# Sch_Dr_General.net
KiCad netlist of a schematic drawn in Altium Designer
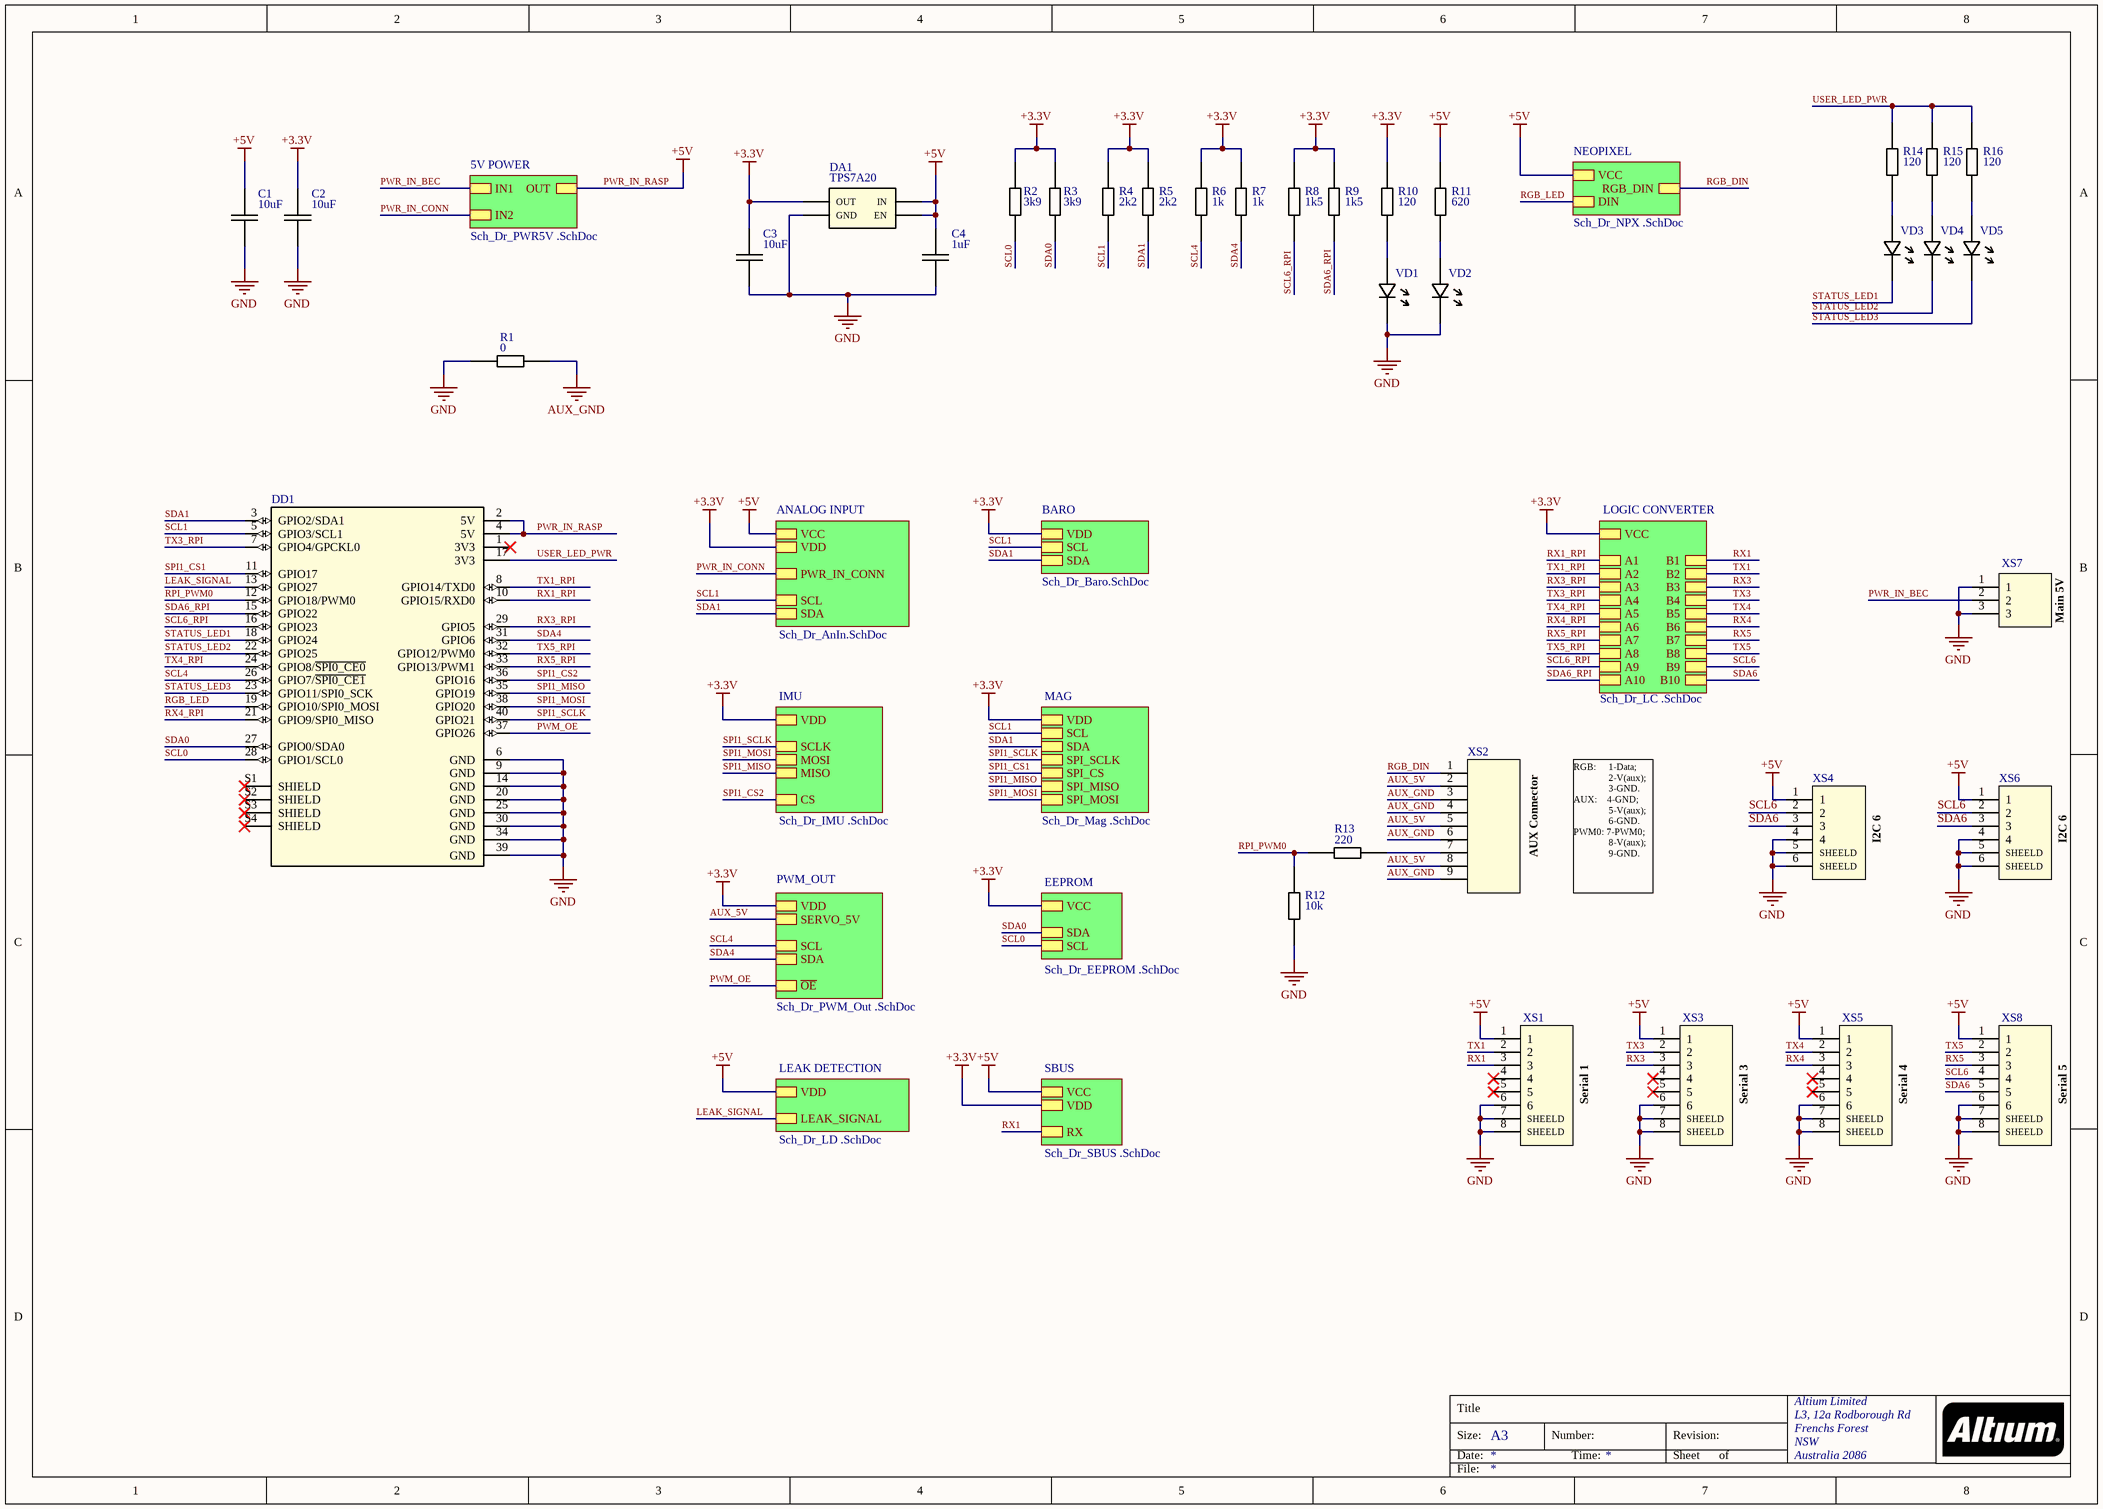
[diagram p0: Sch_Dr_General.SchDoc]

(export (version "E")
  (design (tool "Eeschema 10.0.6"))
  (components
    (comp (ref "C1")
      (value "10uF")
      (footprint "Cap_0603")
      (description "CC0603KRX5R7BB106")
      (libsource (lib "Dr_lib") (part "Cap_"))
    )
    (comp (ref "C2")
      (value "10uF")
      (footprint "Cap_0603")
      (description "CC0603KRX5R7BB106")
      (libsource (lib "Dr_lib") (part "Cap_"))
    )
    (comp (ref "C3")
      (value "10uF")
      (footprint "Cap_0603")
      (description "CC0603KRX5R7BB106")
      (libsource (lib "Dr_lib") (part "Cap_"))
    )
    (comp (ref "C4")
      (value "1uF")
      (footprint "Cap_0603")
      (description "CC0603JRX7R7BB105")
      (libsource (lib "Dr_lib") (part "Cap_"))
    )
    (comp (ref "DA1")
      (value "TPS7A20")
      (footprint "SOT-23-5")
      (description "High PSRR LDO")
      (libsource (lib "Dr_lib") (part "TPS7A20"))
    )
    (comp (ref "DD1")
      (value "RASPBERRY_PI_4")
      (footprint "MOD_RASPBERRY_PI_4B_4GB")
      (description "BCM2711 Raspberry Pi 4 Model B 4GB - ARMÂ® CortexÂ®-A72 MPU Embedded Evaluation Board")
      (fields (field (name "MF") "Raspberry Pi") (field (name "MP") "RASPBERRY PI 4B/4GB"))
      (libsource (lib "Dr_lib") (part "RASPBERRY_PI_4B_4GB"))
    )
    (comp (ref "R1")
      (value "0")
      (footprint "Res_0603")
      (description "CR-03FL7----0R")
      (libsource (lib "") (part "Res__4"))
    )
    (comp (ref "R2")
      (value "3k9")
      (footprint "Res_0603")
      (description "CR-03FL7---3K9")
      (libsource (lib "Dr_lib") (part "Res_"))
    )
    (comp (ref "R3")
      (value "3k9")
      (footprint "Res_0603")
      (description "CR-03FL7---3K9")
      (libsource (lib "Dr_lib") (part "Res_"))
    )
    (comp (ref "R4")
      (value "2k2")
      (footprint "Res_0603")
      (description "CR-03FL7---2K2")
      (libsource (lib "") (part "Res__2"))
    )
    (comp (ref "R5")
      (value "2k2")
      (footprint "Res_0603")
      (description "CR-03FL7---2K2")
      (libsource (lib "") (part "Res__2"))
    )
    (comp (ref "R6")
      (value "1k")
      (footprint "Res_0603")
      (description "CR-03FL7----1K")
      (libsource (lib "") (part "Res__2"))
    )
    (comp (ref "R7")
      (value "1k")
      (footprint "Res_0603")
      (description "CR-03FL7----1K")
      (libsource (lib "") (part "Res__2"))
    )
    (comp (ref "R8")
      (value "1k5")
      (footprint "Res_0603")
      (description "CR-03FL7---1K5")
      (libsource (lib "") (part "Res__2"))
    )
    (comp (ref "R9")
      (value "1k5")
      (footprint "Res_0603")
      (description "CR-03FL7---1K5")
      (libsource (lib "") (part "Res__5"))
    )
    (comp (ref "R10")
      (value "120")
      (footprint "Res_0603")
      (description "CR-03FL7--120R")
      (libsource (lib "") (part "Res__2"))
    )
    (comp (ref "R11")
      (value "620")
      (footprint "Res_0603")
      (description "CR-03FL7--620R")
      (libsource (lib "") (part "Res__2"))
    )
    (comp (ref "R12")
      (value "10k")
      (footprint "Res_0603")
      (description "CR-03FL7---10K")
      (libsource (lib "") (part "Res__3"))
    )
    (comp (ref "R13")
      (value "220")
      (footprint "Res_0603")
      (description "CR-03FL7--220R")
      (libsource (lib "") (part "Res__6"))
    )
    (comp (ref "R14")
      (value "120")
      (footprint "Res_0603")
      (description "CR-03FL7--120R")
      (libsource (lib "") (part "Res__1"))
    )
    (comp (ref "R15")
      (value "120")
      (footprint "Res_0603")
      (description "CR-03FL7---120R")
      (libsource (lib "") (part "Res__1"))
    )
    (comp (ref "R16")
      (value "120")
      (footprint "Res_0603")
      (description "CR-03FL7--120R")
      (libsource (lib "") (part "Res__1"))
    )
    (comp (ref "VD1")
      (value "TO-1608BC-PG")
      (footprint "0603_LED")
      (description "SMD LED Green")
      (libsource (lib "Dr_lib") (part "LED_"))
    )
    (comp (ref "VD2")
      (value "TO-1608BC-PG")
      (footprint "0603_LED")
      (description "SMD LED Green")
      (libsource (lib "Dr_lib") (part "LED_"))
    )
    (comp (ref "VD3")
      (value "TO-1608BC-PG")
      (footprint "0603_LED")
      (description "SMD LED Green")
      (libsource (lib "Dr_lib") (part "LED_"))
    )
    (comp (ref "VD4")
      (value "TO-1608BC-PG")
      (footprint "0603_LED")
      (description "SMD LED Green")
      (libsource (lib "Dr_lib") (part "LED_"))
    )
    (comp (ref "VD5")
      (value "TO-1608BC-PG")
      (footprint "0603_LED")
      (description "SMD LED Green")
      (libsource (lib "Dr_lib") (part "LED_"))
    )
    (comp (ref "XS1")
      (value "BM06B-GHS-TBT(LF)(SN)(N)")
      (footprint "BM06B-GHS-TBT")
      (libsource (lib "Dr_lib") (part "BM06B-GHS-TBT(LF)(SN)(N)"))
    )
    (comp (ref "XS2") (value "PLS-9") (footprint "AUX_CON") (libsource (lib "Dr_lib") (part "AUX_CON")))
    (comp (ref "XS3")
      (value "BM06B-GHS-TBT(LF)(SN)(N)")
      (footprint "BM06B-GHS-TBT")
      (libsource (lib "Dr_lib") (part "BM06B-GHS-TBT(LF)(SN)(N)"))
    )
    (comp (ref "XS4")
      (value "BM04B-GHS-TBT(LF)(SN)(N)")
      (footprint "BM04B-GHS-TBT")
      (libsource (lib "Dr_lib") (part "BM04B-GHS-TBT(LF)(SN)(N)"))
    )
    (comp (ref "XS5")
      (value "BM06B-GHS-TBT(LF)(SN)(N)")
      (footprint "BM06B-GHS-TBT")
      (libsource (lib "Dr_lib") (part "BM06B-GHS-TBT(LF)(SN)(N)"))
    )
    (comp (ref "XS6")
      (value "BM04B-GHS-TBT(LF)(SN)(N)")
      (footprint "BM04B-GHS-TBT")
      (libsource (lib "Dr_lib") (part "BM04B-GHS-TBT(LF)(SN)(N)"))
    )
    (comp (ref "XS7") (value "PLS-3") (footprint "3X") (libsource (lib "Dr_lib") (part "PLS-3")))
    (comp (ref "XS8")
      (value "BM06B-GHS-TBT(LF)(SN)(N)")
      (footprint "BM06B-GHS-TBT")
      (libsource (lib "Dr_lib") (part "BM06B-GHS-TBT(LF)(SN)(N)"))
    )
  )
  (nets
    (net (code "1") (name "+3.3V") (class "Default")
      (node (ref "C2") (pin "2") (pinfunction "2_2") (pintype "passive"))
      (node (ref "C3") (pin "2") (pinfunction "2_2") (pintype "passive"))
      (node (ref "DA1") (pin "5") (pinfunction "OUT_5") (pintype "passive"))
      (node (ref "R10") (pin "1") (pinfunction "1_1") (pintype "passive"))
      (node (ref "R2") (pin "2") (pinfunction "2_2") (pintype "passive"))
      (node (ref "R3") (pin "2") (pinfunction "2_2") (pintype "passive"))
      (node (ref "R4") (pin "1") (pinfunction "1_1") (pintype "passive"))
      (node (ref "R5") (pin "1") (pinfunction "1_1") (pintype "passive"))
      (node (ref "R6") (pin "1") (pinfunction "1_1") (pintype "passive"))
      (node (ref "R7") (pin "1") (pinfunction "1_1") (pintype "passive"))
      (node (ref "R8") (pin "1") (pinfunction "1_1") (pintype "passive"))
      (node (ref "R9") (pin "1") (pinfunction "1_1") (pintype "passive"))
    )
    (net (code "2") (name "+5V") (class "Default")
      (node (ref "C1") (pin "2") (pinfunction "2_2") (pintype "passive"))
      (node (ref "C4") (pin "2") (pinfunction "2_2") (pintype "passive"))
      (node (ref "DA1") (pin "1") (pinfunction "IN_1") (pintype "passive"))
      (node (ref "DA1") (pin "3") (pinfunction "EN_3") (pintype "passive"))
      (node (ref "DD1") (pin "2") (pinfunction "5V_2") (pintype "power_in"))
      (node (ref "DD1") (pin "4") (pinfunction "5V_4") (pintype "power_in"))
      (node (ref "R11") (pin "1") (pinfunction "1_1") (pintype "passive"))
      (node (ref "XS1") (pin "1") (pinfunction "1_1") (pintype "passive"))
      (node (ref "XS3") (pin "1") (pinfunction "1_1") (pintype "passive"))
      (node (ref "XS4") (pin "1") (pinfunction "1_1") (pintype "passive"))
      (node (ref "XS5") (pin "1") (pinfunction "1_1") (pintype "passive"))
      (node (ref "XS6") (pin "1") (pinfunction "1_1") (pintype "passive"))
      (node (ref "XS8") (pin "1") (pinfunction "1_1") (pintype "passive"))
    )
    (net (code "3") (name "/AUX_5V") (class "Default")
      (node (ref "XS2") (pin "2") (pinfunction "2_2") (pintype "passive"))
      (node (ref "XS2") (pin "5") (pinfunction "5_5") (pintype "passive"))
      (node (ref "XS2") (pin "8") (pinfunction "8_8") (pintype "passive"))
    )
    (net (code "6") (name "/LEAK_SIGNAL") (class "Default")
      (node (ref "DD1") (pin "13") (pinfunction "GPIO27_13") (pintype "bidirectional"))
    )
    (net (code "8") (name "/PWM_OE") (class "Default")
      (node (ref "DD1") (pin "37") (pinfunction "GPIO26_37") (pintype "bidirectional"))
    )
    (net (code "9") (name "/PWR_IN_BEC") (class "Default")
      (node (ref "XS7") (pin "2") (pinfunction "2_2") (pintype "passive"))
    )
    (net (code "11") (name "/RGB_DIN") (class "Default")
      (node (ref "XS2") (pin "1") (pinfunction "1_1") (pintype "passive"))
    )
    (net (code "13") (name "/RGB_LED") (class "Default")
      (node (ref "DD1") (pin "19") (pinfunction "GPIO10/SPI0_MOSI_19") (pintype "bidirectional"))
    )
    (net (code "14") (name "/RPI_PWM0") (class "Default")
      (node (ref "DD1") (pin "12") (pinfunction "GPIO18/PWM0_12") (pintype "bidirectional"))
      (node (ref "R12") (pin "1") (pinfunction "1_1") (pintype "passive"))
      (node (ref "R13") (pin "1") (pinfunction "1_1") (pintype "passive"))
    )
    (net (code "15") (name "/RX1") (class "Default")
      (node (ref "XS1") (pin "3") (pinfunction "3_3") (pintype "passive"))
    )
    (net (code "16") (name "/RX1_RPI") (class "Default")
      (node (ref "DD1") (pin "10") (pinfunction "GPIO15/RXD0_10") (pintype "bidirectional"))
    )
    (net (code "17") (name "/RX3") (class "Default")
      (node (ref "XS3") (pin "3") (pinfunction "3_3") (pintype "passive"))
    )
    (net (code "18") (name "/RX3_RPI") (class "Default")
      (node (ref "DD1") (pin "29") (pinfunction "GPIO5_29") (pintype "bidirectional"))
    )
    (net (code "19") (name "/RX4") (class "Default")
      (node (ref "XS5") (pin "3") (pinfunction "3_3") (pintype "passive"))
    )
    (net (code "20") (name "/RX4_RPI") (class "Default")
      (node (ref "DD1") (pin "21") (pinfunction "GPIO9/SPI0_MISO_21") (pintype "bidirectional"))
    )
    (net (code "21") (name "/RX5") (class "Default")
      (node (ref "XS8") (pin "3") (pinfunction "3_3") (pintype "passive"))
    )
    (net (code "22") (name "/RX5_RPI") (class "Default")
      (node (ref "DD1") (pin "33") (pinfunction "GPIO13/PWM1_33") (pintype "bidirectional"))
    )
    (net (code "23") (name "/SCL0") (class "Default")
      (node (ref "DD1") (pin "28") (pinfunction "GPIO1/SCL0_28") (pintype "bidirectional"))
      (node (ref "R2") (pin "1") (pinfunction "1_1") (pintype "passive"))
    )
    (net (code "24") (name "/SCL1") (class "Default")
      (node (ref "DD1") (pin "5") (pinfunction "GPIO3/SCL1_5") (pintype "bidirectional"))
      (node (ref "R4") (pin "2") (pinfunction "2_2") (pintype "passive"))
    )
    (net (code "25") (name "/SCL4") (class "Default")
      (node (ref "DD1") (pin "26") (pinfunction "GPIO7/~{SPI0_CE1}_26") (pintype "bidirectional"))
      (node (ref "R6") (pin "2") (pinfunction "2_2") (pintype "passive"))
    )
    (net (code "26") (name "/SCL6") (class "Default")
      (node (ref "XS4") (pin "2") (pinfunction "2_2") (pintype "passive"))
      (node (ref "XS6") (pin "2") (pinfunction "2_2") (pintype "passive"))
      (node (ref "XS8") (pin "4") (pinfunction "4_4") (pintype "passive"))
    )
    (net (code "27") (name "/SCL6_RPI") (class "Default")
      (node (ref "DD1") (pin "16") (pinfunction "GPIO23_16") (pintype "bidirectional"))
      (node (ref "R8") (pin "2") (pinfunction "2_2") (pintype "passive"))
    )
    (net (code "28") (name "/SDA0") (class "Default")
      (node (ref "DD1") (pin "27") (pinfunction "GPIO0/SDA0_27") (pintype "bidirectional"))
      (node (ref "R3") (pin "1") (pinfunction "1_1") (pintype "passive"))
    )
    (net (code "29") (name "/SDA1") (class "Default")
      (node (ref "DD1") (pin "3") (pinfunction "GPIO2/SDA1_3") (pintype "bidirectional"))
      (node (ref "R5") (pin "2") (pinfunction "2_2") (pintype "passive"))
    )
    (net (code "30") (name "/SDA4") (class "Default")
      (node (ref "DD1") (pin "31") (pinfunction "GPIO6_31") (pintype "bidirectional"))
      (node (ref "R7") (pin "2") (pinfunction "2_2") (pintype "passive"))
    )
    (net (code "31") (name "/SDA6") (class "Default")
      (node (ref "XS4") (pin "3") (pinfunction "3_3") (pintype "passive"))
      (node (ref "XS6") (pin "3") (pinfunction "3_3") (pintype "passive"))
      (node (ref "XS8") (pin "5") (pinfunction "5_5") (pintype "passive"))
    )
    (net (code "32") (name "/SDA6_RPI") (class "Default")
      (node (ref "DD1") (pin "15") (pinfunction "GPIO22_15") (pintype "bidirectional"))
      (node (ref "R9") (pin "2") (pinfunction "2_2") (pintype "passive"))
    )
    (net (code "33") (name "/SPI1_CS1") (class "Default")
      (node (ref "DD1") (pin "11") (pinfunction "GPIO17_11") (pintype "bidirectional"))
    )
    (net (code "34") (name "/SPI1_CS2") (class "Default")
      (node (ref "DD1") (pin "36") (pinfunction "GPIO16_36") (pintype "bidirectional"))
    )
    (net (code "35") (name "/SPI1_MISO") (class "Default")
      (node (ref "DD1") (pin "35") (pinfunction "GPIO19_35") (pintype "bidirectional"))
    )
    (net (code "36") (name "/SPI1_MOSI") (class "Default")
      (node (ref "DD1") (pin "38") (pinfunction "GPIO20_38") (pintype "bidirectional"))
    )
    (net (code "37") (name "/SPI1_SCLK") (class "Default")
      (node (ref "DD1") (pin "40") (pinfunction "GPIO21_40") (pintype "bidirectional"))
    )
    (net (code "38") (name "/STATUS_LED1") (class "Default")
      (node (ref "DD1") (pin "18") (pinfunction "GPIO24_18") (pintype "bidirectional"))
      (node (ref "VD3") (pin "1") (pinfunction "K_1") (pintype "passive"))
    )
    (net (code "39") (name "/STATUS_LED2") (class "Default")
      (node (ref "DD1") (pin "22") (pinfunction "GPIO25_22") (pintype "bidirectional"))
      (node (ref "VD4") (pin "1") (pinfunction "K_1") (pintype "passive"))
    )
    (net (code "40") (name "/STATUS_LED3") (class "Default")
      (node (ref "DD1") (pin "23") (pinfunction "GPIO11/SPI0_SCK_23") (pintype "bidirectional"))
      (node (ref "VD5") (pin "1") (pinfunction "K_1") (pintype "passive"))
    )
    (net (code "41") (name "/TX1") (class "Default")
      (node (ref "XS1") (pin "2") (pinfunction "2_2") (pintype "passive"))
    )
    (net (code "42") (name "/TX1_RPI") (class "Default")
      (node (ref "DD1") (pin "8") (pinfunction "GPIO14/TXD0_8") (pintype "bidirectional"))
    )
    (net (code "43") (name "/TX3") (class "Default")
      (node (ref "XS3") (pin "2") (pinfunction "2_2") (pintype "passive"))
    )
    (net (code "44") (name "/TX3_RPI") (class "Default")
      (node (ref "DD1") (pin "7") (pinfunction "GPIO4/GPCKL0_7") (pintype "bidirectional"))
    )
    (net (code "45") (name "/TX4") (class "Default")
      (node (ref "XS5") (pin "2") (pinfunction "2_2") (pintype "passive"))
    )
    (net (code "46") (name "/TX4_RPI") (class "Default")
      (node (ref "DD1") (pin "24") (pinfunction "GPIO8/~{SPI0_CE0}_24") (pintype "bidirectional"))
    )
    (net (code "47") (name "/TX5") (class "Default")
      (node (ref "XS8") (pin "2") (pinfunction "2_2") (pintype "passive"))
    )
    (net (code "48") (name "/TX5_RPI") (class "Default")
      (node (ref "DD1") (pin "32") (pinfunction "GPIO12/PWM0_32") (pintype "bidirectional"))
    )
    (net (code "49") (name "/USER_LED_PWR") (class "Default")
      (node (ref "DD1") (pin "17") (pinfunction "3V3_17") (pintype "power_in"))
      (node (ref "R14") (pin "1") (pinfunction "1_1") (pintype "passive"))
      (node (ref "R15") (pin "1") (pinfunction "1_1") (pintype "passive"))
      (node (ref "R16") (pin "1") (pinfunction "1_1") (pintype "passive"))
    )
    (net (code "51") (name "AUX_GND") (class "Default")
      (node (ref "R1") (pin "2") (pinfunction "2_2") (pintype "passive"))
      (node (ref "XS2") (pin "3") (pinfunction "3_3") (pintype "passive"))
      (node (ref "XS2") (pin "4") (pinfunction "4_4") (pintype "passive"))
      (node (ref "XS2") (pin "6") (pinfunction "6_6") (pintype "passive"))
      (node (ref "XS2") (pin "9") (pinfunction "9_9") (pintype "passive"))
    )
    (net (code "52") (name "GND") (class "Default")
      (node (ref "C1") (pin "1") (pinfunction "1_1") (pintype "passive"))
      (node (ref "C2") (pin "1") (pinfunction "1_1") (pintype "passive"))
      (node (ref "C3") (pin "1") (pinfunction "1_1") (pintype "passive"))
      (node (ref "C4") (pin "1") (pinfunction "1_1") (pintype "passive"))
      (node (ref "DA1") (pin "2") (pinfunction "GND_2") (pintype "passive"))
      (node (ref "DD1") (pin "14") (pinfunction "GND_14") (pintype "power_in"))
      (node (ref "DD1") (pin "20") (pinfunction "GND_20") (pintype "power_in"))
      (node (ref "DD1") (pin "25") (pinfunction "GND_25") (pintype "power_in"))
      (node (ref "DD1") (pin "30") (pinfunction "GND_30") (pintype "power_in"))
      (node (ref "DD1") (pin "34") (pinfunction "GND_34") (pintype "power_in"))
      (node (ref "DD1") (pin "39") (pinfunction "GND_39") (pintype "power_in"))
      (node (ref "DD1") (pin "6") (pinfunction "GND_6") (pintype "power_in"))
      (node (ref "DD1") (pin "9") (pinfunction "GND_9") (pintype "power_in"))
      (node (ref "R1") (pin "1") (pinfunction "1_1") (pintype "passive"))
      (node (ref "R12") (pin "2") (pinfunction "2_2") (pintype "passive"))
      (node (ref "VD1") (pin "1") (pinfunction "K_1") (pintype "passive"))
      (node (ref "VD2") (pin "1") (pinfunction "K_1") (pintype "passive"))
      (node (ref "XS1") (pin "6") (pinfunction "6_6") (pintype "passive"))
      (node (ref "XS1") (pin "7") (pinfunction "SHEELD_7") (pintype "passive"))
      (node (ref "XS1") (pin "8") (pinfunction "SHEELD_8") (pintype "passive"))
      (node (ref "XS3") (pin "6") (pinfunction "6_6") (pintype "passive"))
      (node (ref "XS3") (pin "7") (pinfunction "SHEELD_7") (pintype "passive"))
      (node (ref "XS3") (pin "8") (pinfunction "SHEELD_8") (pintype "passive"))
      (node (ref "XS4") (pin "4") (pinfunction "4_4") (pintype "passive"))
      (node (ref "XS4") (pin "5") (pinfunction "SHEELD_5") (pintype "passive"))
      (node (ref "XS4") (pin "6") (pinfunction "SHEELD_6") (pintype "passive"))
      (node (ref "XS5") (pin "6") (pinfunction "6_6") (pintype "passive"))
      (node (ref "XS5") (pin "7") (pinfunction "SHEELD_7") (pintype "passive"))
      (node (ref "XS5") (pin "8") (pinfunction "SHEELD_8") (pintype "passive"))
      (node (ref "XS6") (pin "4") (pinfunction "4_4") (pintype "passive"))
      (node (ref "XS6") (pin "5") (pinfunction "SHEELD_5") (pintype "passive"))
      (node (ref "XS6") (pin "6") (pinfunction "SHEELD_6") (pintype "passive"))
      (node (ref "XS7") (pin "1") (pinfunction "1_1") (pintype "passive"))
      (node (ref "XS7") (pin "3") (pinfunction "3_3") (pintype "passive"))
      (node (ref "XS8") (pin "6") (pinfunction "6_6") (pintype "passive"))
      (node (ref "XS8") (pin "7") (pinfunction "SHEELD_7") (pintype "passive"))
      (node (ref "XS8") (pin "8") (pinfunction "SHEELD_8") (pintype "passive"))
    )
    (net (code "53") (name "Net-(R13-Pad2)") (class "Default")
      (node (ref "R13") (pin "2") (pinfunction "2_2") (pintype "passive"))
      (node (ref "XS2") (pin "7") (pinfunction "7_7") (pintype "passive"))
    )
    (net (code "54") (name "Net-(VD1-A)") (class "Default")
      (node (ref "R10") (pin "2") (pinfunction "2_2") (pintype "passive"))
      (node (ref "VD1") (pin "2") (pinfunction "A_2") (pintype "passive"))
    )
    (net (code "55") (name "Net-(VD2-A)") (class "Default")
      (node (ref "R11") (pin "2") (pinfunction "2_2") (pintype "passive"))
      (node (ref "VD2") (pin "2") (pinfunction "A_2") (pintype "passive"))
    )
    (net (code "56") (name "Net-(VD3-A)") (class "Default")
      (node (ref "R14") (pin "2") (pinfunction "2_2") (pintype "passive"))
      (node (ref "VD3") (pin "2") (pinfunction "A_2") (pintype "passive"))
    )
    (net (code "57") (name "Net-(VD4-A)") (class "Default")
      (node (ref "R15") (pin "2") (pinfunction "2_2") (pintype "passive"))
      (node (ref "VD4") (pin "2") (pinfunction "A_2") (pintype "passive"))
    )
    (net (code "58") (name "Net-(VD5-A)") (class "Default")
      (node (ref "R16") (pin "2") (pinfunction "2_2") (pintype "passive"))
      (node (ref "VD5") (pin "2") (pinfunction "A_2") (pintype "passive"))
    )
    (net (code "59") (name "unconnected-(DD1-3V3-Pad1)") (class "Default")
      (node (ref "DD1") (pin "1") (pinfunction "3V3_1") (pintype "power_in+no_connect"))
    )
    (net (code "60") (name "unconnected-(DD1-SHIELD-PadS1)") (class "Default")
      (node (ref "DD1") (pin "S1") (pinfunction "SHIELD_S1") (pintype "power_in+no_connect"))
    )
    (net (code "61") (name "unconnected-(DD1-SHIELD-PadS2)") (class "Default")
      (node (ref "DD1") (pin "S2") (pinfunction "SHIELD_S2") (pintype "power_in+no_connect"))
    )
    (net (code "62") (name "unconnected-(DD1-SHIELD-PadS3)") (class "Default")
      (node (ref "DD1") (pin "S3") (pinfunction "SHIELD_S3") (pintype "power_in+no_connect"))
    )
    (net (code "63") (name "unconnected-(DD1-SHIELD-PadS4)") (class "Default")
      (node (ref "DD1") (pin "S4") (pinfunction "SHIELD_S4") (pintype "power_in+no_connect"))
    )
    (net (code "64") (name "unconnected-(XS1-Pad4)") (class "Default")
      (node (ref "XS1") (pin "4") (pinfunction "4_4") (pintype "passive+no_connect"))
    )
    (net (code "65") (name "unconnected-(XS1-Pad5)") (class "Default")
      (node (ref "XS1") (pin "5") (pinfunction "5_5") (pintype "passive+no_connect"))
    )
    (net (code "66") (name "unconnected-(XS3-Pad4)") (class "Default")
      (node (ref "XS3") (pin "4") (pinfunction "4_4") (pintype "passive+no_connect"))
    )
    (net (code "67") (name "unconnected-(XS3-Pad5)") (class "Default")
      (node (ref "XS3") (pin "5") (pinfunction "5_5") (pintype "passive+no_connect"))
    )
    (net (code "68") (name "unconnected-(XS5-Pad4)") (class "Default")
      (node (ref "XS5") (pin "4") (pinfunction "4_4") (pintype "passive+no_connect"))
    )
    (net (code "69") (name "unconnected-(XS5-Pad5)") (class "Default")
      (node (ref "XS5") (pin "5") (pinfunction "5_5") (pintype "passive+no_connect"))
    )
  )
)
